# main.net
KiCad netlist of a schematic drawn in EAGLE
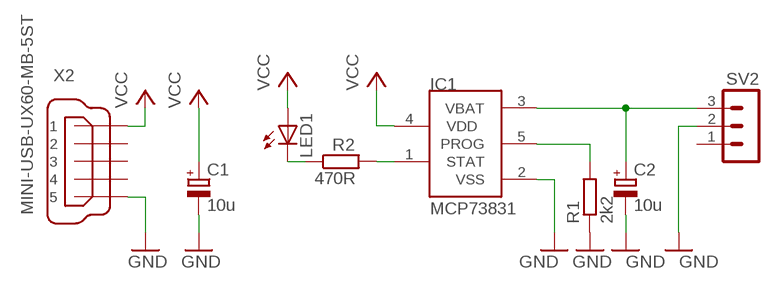
[diagram p0: schematic, sheet 1]

(export (version "E")
  (design (tool "Eeschema 10.0.6"))
  (components
    (comp (ref "C1")
      (value "10u")
      (footprint "eagle-import:SMC_A")
      (libsource (lib "eagle-import") (part "CPOL-EUSMCA"))
    )
    (comp (ref "C2")
      (value "10u")
      (footprint "eagle-import:SMC_A")
      (libsource (lib "eagle-import") (part "CPOL-EUSMCA"))
    )
    (comp (ref "IC1")
      (value "MCP73831")
      (footprint "eagle-import:SOT23-5L")
      (libsource (lib "eagle-import") (part "MCP73831"))
    )
    (comp (ref "LED1")
      (value "LEDSML0805")
      (footprint "eagle-import:SML0805")
      (libsource (lib "eagle-import") (part "LEDSML0805"))
    )
    (comp (ref "R1")
      (value "2k2")
      (footprint "eagle-import:R1206")
      (libsource (lib "eagle-import") (part "R-EU_R1206"))
    )
    (comp (ref "R2")
      (value "470R")
      (footprint "eagle-import:R1206")
      (libsource (lib "eagle-import") (part "R-EU_R1206"))
    )
    (comp (ref "SV2")
      (value "MA03-1")
      (footprint "eagle-import:MA03-1")
      (libsource (lib "eagle-import") (part "MA03-1"))
    )
    (comp (ref "X2")
      (value "MINI-USB-UX60-MB-5ST")
      (footprint "eagle-import:UX60-MB-5ST")
      (libsource (lib "eagle-import") (part "MINI-USB-UX60-MB-5ST"))
    )
  )
  (nets
    (net (code "1") (name "GND") (class "Default")
      (node (ref "C1") (pin "-") (pinfunction "-_-") (pintype "passive"))
      (node (ref "C2") (pin "-") (pinfunction "-_-") (pintype "passive"))
      (node (ref "IC1") (pin "2") (pinfunction "VSS_2") (pintype "bidirectional"))
      (node (ref "R1") (pin "1") (pinfunction "1_1") (pintype "passive"))
      (node (ref "SV2") (pin "2") (pinfunction "2_2") (pintype "passive"))
      (node (ref "X2") (pin "5") (pinfunction "5_5") (pintype "input"))
    )
    (net (code "2") (name "Net-(IC1-PROG)") (class "Default")
      (node (ref "IC1") (pin "5") (pinfunction "PROG_5") (pintype "bidirectional"))
      (node (ref "R1") (pin "2") (pinfunction "2_2") (pintype "passive"))
    )
    (net (code "3") (name "Net-(IC1-STAT)") (class "Default")
      (node (ref "IC1") (pin "1") (pinfunction "STAT_1") (pintype "bidirectional"))
      (node (ref "R2") (pin "2") (pinfunction "2_2") (pintype "passive"))
    )
    (net (code "4") (name "Net-(IC1-VBAT)") (class "Default")
      (node (ref "C2") (pin "+") (pinfunction "+_+") (pintype "passive"))
      (node (ref "IC1") (pin "3") (pinfunction "VBAT_3") (pintype "bidirectional"))
      (node (ref "SV2") (pin "3") (pinfunction "3_3") (pintype "passive"))
    )
    (net (code "5") (name "Net-(LED1-PadC)") (class "Default")
      (node (ref "LED1") (pin "C") (pinfunction "C_C") (pintype "passive"))
      (node (ref "R2") (pin "1") (pinfunction "1_1") (pintype "passive"))
    )
    (net (code "6") (name "VCC") (class "Default")
      (node (ref "C1") (pin "+") (pinfunction "+_+") (pintype "passive"))
      (node (ref "IC1") (pin "4") (pinfunction "VDD_4") (pintype "bidirectional"))
      (node (ref "LED1") (pin "A") (pinfunction "A_A") (pintype "passive"))
      (node (ref "X2") (pin "1") (pinfunction "1_1") (pintype "input"))
    )
    (net (code "7") (name "unconnected-(SV2-Pad1)") (class "Default")
      (node (ref "SV2") (pin "1") (pinfunction "1_1") (pintype "passive"))
    )
    (net (code "8") (name "unconnected-(X2-Pad2)") (class "Default")
      (node (ref "X2") (pin "2") (pinfunction "2_2") (pintype "input"))
    )
    (net (code "9") (name "unconnected-(X2-Pad3)") (class "Default")
      (node (ref "X2") (pin "3") (pinfunction "3_3") (pintype "input"))
    )
    (net (code "10") (name "unconnected-(X2-Pad4)") (class "Default")
      (node (ref "X2") (pin "4") (pinfunction "4_4") (pintype "input"))
    )
  )
)
